# main.net
KiCad netlist of a schematic drawn in Altium Designer
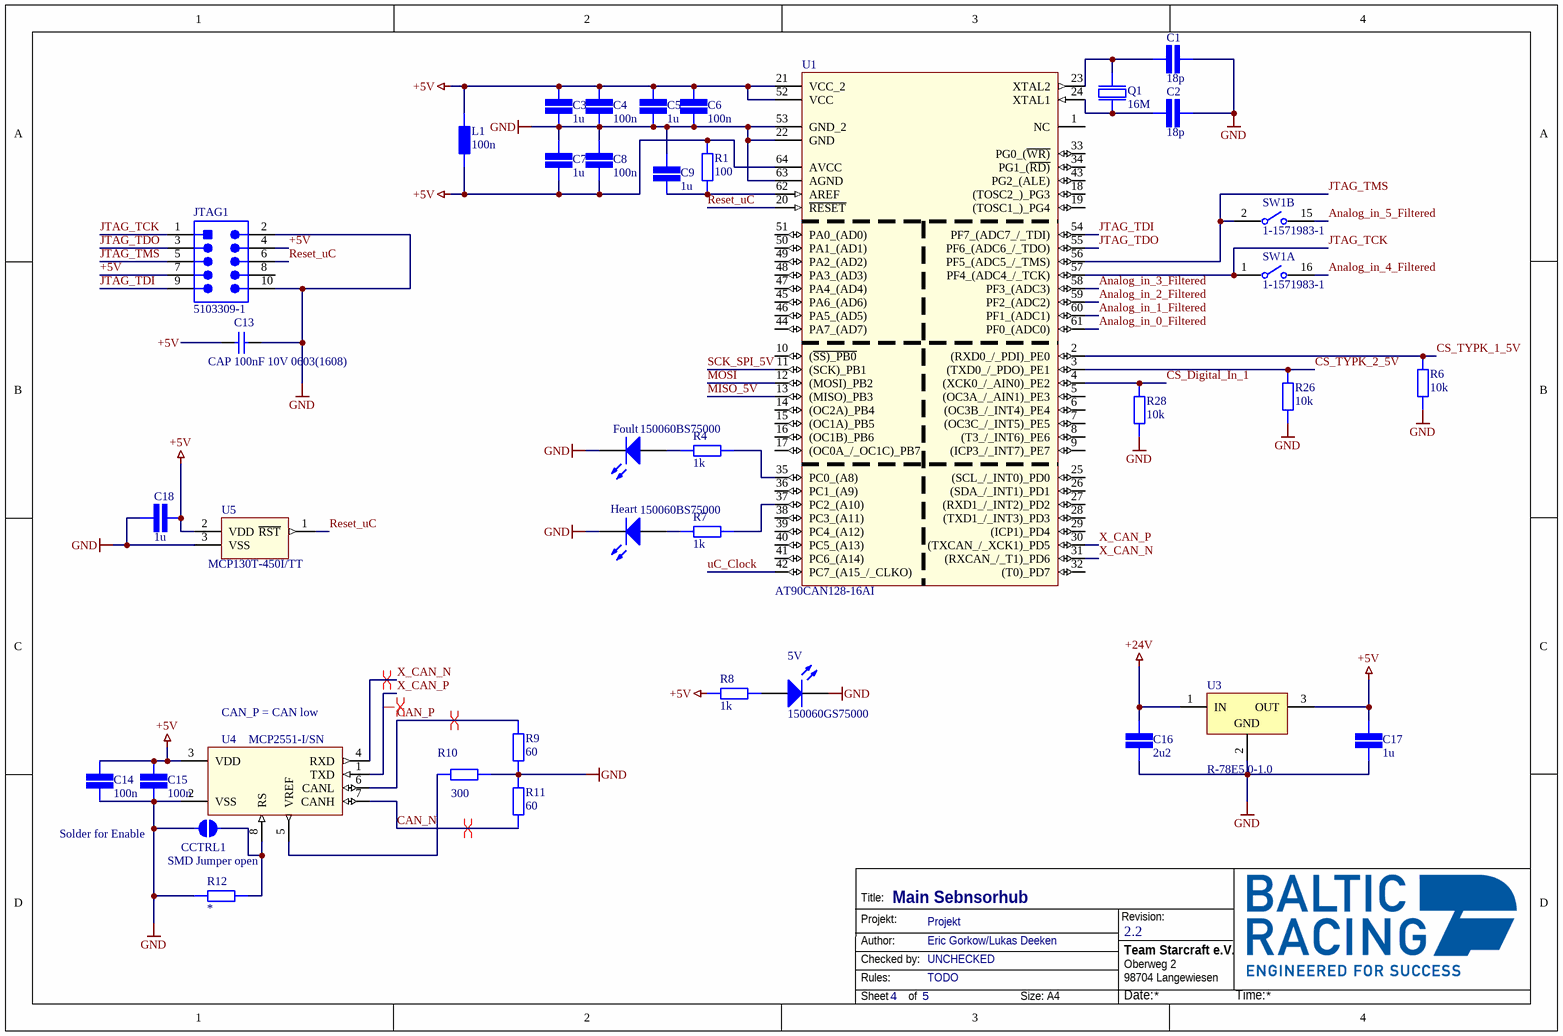
[diagram p0: main.SchDoc]

(export (version "E")
  (design (tool "Eeschema 10.0.6"))
  (components
    (comp (ref "5V")
      (value "150060GS75000")
      (footprint "0603_A")
      (description "SMD mono-color Chip LED, WL-SMCW, Green")
      (fields (field (name "MANUFACTURER") "Wuerth Elektronik"))
      (libsource (lib "Altium Content Vault") (part "WE-LED_K1A2-2"))
    )
    (comp (ref "C1")
      (value "18p")
      (footprint "CAP 0603/1608")
      (description "Capacitor with multiple Footprints")
      (fields (field (name "Comment") "SMD Capacitor"))
      (libsource (lib "") (part "SMD Capacitor_1"))
    )
    (comp (ref "C2")
      (value "18p")
      (footprint "CAP 0603/1608")
      (description "Capacitor with multiple Footprints")
      (fields (field (name "Comment") "SMD Capacitor"))
      (libsource (lib "") (part "SMD Capacitor_1"))
    )
    (comp (ref "C3")
      (value "1u")
      (footprint "CAP 0603/1608")
      (description "Capacitor with multiple Footprints")
      (fields (field (name "Comment") "SMD Capacitor"))
      (libsource (lib "Standardbauteile") (part "SMD Capacitor"))
    )
    (comp (ref "C4")
      (value "100n")
      (footprint "CAP 0603/1608")
      (description "Capacitor with multiple Footprints")
      (fields (field (name "Comment") "SMD Capacitor"))
      (libsource (lib "Standardbauteile") (part "SMD Capacitor"))
    )
    (comp (ref "C5")
      (value "1u")
      (footprint "CAP 0603/1608")
      (description "Capacitor with multiple Footprints")
      (fields (field (name "Comment") "SMD Capacitor"))
      (libsource (lib "Standardbauteile") (part "SMD Capacitor"))
    )
    (comp (ref "C6")
      (value "100n")
      (footprint "CAP 0603/1608")
      (description "Capacitor with multiple Footprints")
      (fields (field (name "Comment") "SMD Capacitor"))
      (libsource (lib "Standardbauteile") (part "SMD Capacitor"))
    )
    (comp (ref "C7")
      (value "1u")
      (footprint "CAP 0603/1608")
      (description "Capacitor with multiple Footprints")
      (fields (field (name "Comment") "SMD Capacitor"))
      (libsource (lib "Standardbauteile") (part "SMD Capacitor"))
    )
    (comp (ref "C8")
      (value "100n")
      (footprint "CAP 0603/1608")
      (description "Capacitor with multiple Footprints")
      (fields (field (name "Comment") "SMD Capacitor"))
      (libsource (lib "Standardbauteile") (part "SMD Capacitor"))
    )
    (comp (ref "C9")
      (value "1u")
      (footprint "CAP 0603/1608")
      (description "Capacitor with multiple Footprints")
      (fields (field (name "Comment") "SMD Capacitor"))
      (libsource (lib "Standardbauteile") (part "SMD Capacitor"))
    )
    (comp (ref "C13")
      (value "CAP 100nF 10V 0603(1608)")
      (footprint "CAPC0603(1608)100_L")
      (description "CAP 100nF 10V ±5% 0603 (1608 Metric) Thickness 1mm SMD")
      (fields (field (name "TOLERANCE") "Â±5%"))
      (libsource (lib "Altium Content Vault") (part "CAP"))
    )
    (comp (ref "C14")
      (value "100n")
      (footprint "CAP 0603/1608")
      (description "Capacitor with multiple Footprints")
      (fields (field (name "Comment") "SMD Capacitor"))
      (libsource (lib "Standardbauteile") (part "SMD Capacitor"))
    )
    (comp (ref "C15")
      (value "100n")
      (footprint "CAP 0603/1608")
      (description "Capacitor with multiple Footprints")
      (fields (field (name "Comment") "SMD Capacitor"))
      (libsource (lib "Standardbauteile") (part "SMD Capacitor"))
    )
    (comp (ref "C16")
      (value "2u2")
      (footprint "CAP 0603/1608")
      (description "Capacitor with multiple Footprints")
      (fields (field (name "Comment") "SMD Capacitor"))
      (libsource (lib "Standardbauteile") (part "SMD Capacitor"))
    )
    (comp (ref "C17")
      (value "1u")
      (footprint "CAP 0603/1608")
      (description "Capacitor with multiple Footprints")
      (fields (field (name "Comment") "SMD Capacitor"))
      (libsource (lib "Standardbauteile") (part "SMD Capacitor"))
    )
    (comp (ref "C18")
      (value "1u")
      (footprint "CAP 0603/1608")
      (description "Capacitor with multiple Footprints")
      (fields (field (name "Comment") "SMD Capacitor"))
      (libsource (lib "") (part "SMD Capacitor_1"))
    )
    (comp (ref "CCTRL1")
      (value "SMD Jumper open")
      (footprint "SMD-JUMPER-OPEN")
      (libsource (lib "Standardbauteile") (part "SMD Jumper open"))
    )
    (comp (ref "Foult")
      (value "150060BS75000")
      (footprint "0603_A")
      (description "SMD mono-color Chip LED, WL-SMCW, Blue")
      (fields (field (name "MANUFACTURER") "Wuerth Elektronik"))
      (libsource (lib "Altium Content Vault") (part "WE-LED_K1A2-2"))
    )
    (comp (ref "Heart")
      (value "150060BS75000")
      (footprint "0603_A")
      (description "SMD mono-color Chip LED, WL-SMCW, Blue")
      (fields (field (name "MANUFACTURER") "Wuerth Elektronik"))
      (libsource (lib "Altium Content Vault") (part "WE-LED_K1A2-2"))
    )
    (comp (ref "JTAG1")
      (value "5103309-1")
      (footprint "TECO-5103309-1_V")
      (fields (field (name "MANUFACTURER") "TE Connectivity"))
      (libsource (lib "Altium Content Vault") (part "CN-2P-M-R10"))
    )
    (comp (ref "L1")
      (value "100n")
      (footprint "STACKPOLE CSR0603")
      (fields (field (name "Comment") "SMD Inductor"))
      (libsource (lib "Standardbauteile") (part "SMD Inductor"))
    )
    (comp (ref "Q1")
      (value "16M")
      (footprint "NDK NX5032GA")
      (description "16 MHz Quartz")
      (libsource (lib "Standardbauteile") (part "16 MHz Quartz"))
    )
    (comp (ref "R1")
      (value "100")
      (footprint "STACKPOLE CSR0603")
      (description "Resistor with multiple footprints")
      (fields (field (name "Comment") "SMD Resistor"))
      (libsource (lib "Standardbauteile") (part "SMD Resistor"))
    )
    (comp (ref "R4")
      (value "1k")
      (footprint "STACKPOLE CSR0603")
      (description "Resistor with multiple footprints")
      (fields (field (name "Comment") "0603 220"))
      (libsource (lib "Standardbauteile") (part "SMD Resistor"))
    )
    (comp (ref "R6")
      (value "10k")
      (footprint "STACKPOLE CSR0603")
      (description "Resistor with multiple footprints")
      (fields (field (name "Comment") "SMD Resistor"))
      (libsource (lib "Standardbauteile") (part "SMD Resistor"))
    )
    (comp (ref "R7")
      (value "1k")
      (footprint "STACKPOLE CSR0603")
      (description "Resistor with multiple footprints")
      (fields (field (name "Comment") "0603 220"))
      (libsource (lib "Standardbauteile") (part "SMD Resistor"))
    )
    (comp (ref "R8")
      (value "1k")
      (footprint "STACKPOLE CSR0603")
      (description "Resistor with multiple footprints")
      (fields (field (name "Comment") "0603 220"))
      (libsource (lib "Standardbauteile") (part "SMD Resistor"))
    )
    (comp (ref "R9")
      (value "60")
      (footprint "STACKPOLE CSR0603")
      (description "Resistor with multiple footprints")
      (fields (field (name "Comment") "SMD Resistor"))
      (libsource (lib "Standardbauteile") (part "SMD Resistor"))
    )
    (comp (ref "R10")
      (value "300")
      (footprint "STACKPOLE CSR0603")
      (description "Resistor with multiple footprints")
      (fields (field (name "Comment") "SMD Resistor"))
      (libsource (lib "Standardbauteile") (part "SMD Resistor"))
    )
    (comp (ref "R11")
      (value "60")
      (footprint "STACKPOLE CSR0603")
      (description "Resistor with multiple footprints")
      (fields (field (name "Comment") "SMD Resistor"))
      (libsource (lib "Standardbauteile") (part "SMD Resistor"))
    )
    (comp (ref "R12")
      (value "SMD Resistor")
      (footprint "STACKPOLE CSR0603")
      (description "Resistor with multiple footprints")
      (fields (field (name "ALTIUM_VALUE") "*"))
      (libsource (lib "Standardbauteile") (part "SMD Resistor"))
    )
    (comp (ref "R26")
      (value "10k")
      (footprint "STACKPOLE CSR0603")
      (description "Resistor with multiple footprints")
      (fields (field (name "Comment") "SMD Resistor"))
      (libsource (lib "Standardbauteile") (part "SMD Resistor"))
    )
    (comp (ref "R28")
      (value "10k")
      (footprint "STACKPOLE CSR0603")
      (description "Resistor with multiple footprints")
      (fields (field (name "Comment") "SMD Resistor"))
      (libsource (lib "Standardbauteile") (part "SMD Resistor"))
    )
    (comp (ref "SW1")
      (value "1-1571983-1")
      (footprint "FP-1-1571983-1-MFG")
      (description "SWITCH SLIDE DIP SPST 25MA 24V")
      (fields
        (field (name "MANUFACTURER") "TE Connectivity")
        (field (name "OCTOPART") "https://octopart.com/1-1571983-1-te+connectivity-40115518")
      )
      (libsource (lib "Altium Content Vault") (part "970e54b12a704161c1b4a03f85903bf"))
    )
    (comp (ref "U1")
      (value "AT90CAN128-16AI")
      (footprint "*QFP80P1600X1600X120-64N")
      (description "Ic Mcu 8bit 128kb Flash 64tqfp")
      (fields (field (name "MF") "Microchip"))
      (libsource (lib "Eric") (part "AT90CAN128-16AI"))
    )
    (comp (ref "U3")
      (value "R-78E5.0-1.0")
      (footprint "SIP3_RECOM")
      (description "Nonisolated 5V Switchmode converter")
      (libsource (lib "Standardbauteile") (part "R-78E05-1.0"))
    )
    (comp (ref "U4")
      (value "MCP2551-I/SN")
      (footprint "*SOIC127P600X175-8N")
      (description "MCP2551 Series 5.5 V 1 Mb/s Surface Mount High-Speed CAN Transceiver - SOIC-8")
      (fields (field (name "MF") "Microchip"))
      (libsource (lib "Eric") (part "MCP2551-I/SN"))
    )
    (comp (ref "U5")
      (value "MCP130T-450I/TT")
      (footprint "*SOT95P237X112-3N")
      (description "System Supervisors - Power Supply Monitors with Reset Generators Open Drain Low")
      (fields (field (name "MF") "Microchip") (field (name "MP") "MCP120T-450I/TT"))
      (libsource (lib "Eric") (part "MCP130T-450I/TT"))
    )
  )
  (nets
    (net (code "1") (name "+5V") (class "Default")
      (node (ref "C13") (pin "1") (pinfunction "1_1") (pintype "passive"))
      (node (ref "C14") (pin "2") (pinfunction "2_2") (pintype "passive"))
      (node (ref "C15") (pin "2") (pinfunction "2_2") (pintype "passive"))
      (node (ref "C17") (pin "2") (pinfunction "2_2") (pintype "passive"))
      (node (ref "C18") (pin "1") (pinfunction "1_1") (pintype "passive"))
      (node (ref "C3") (pin "2") (pinfunction "2_2") (pintype "passive"))
      (node (ref "C4") (pin "2") (pinfunction "2_2") (pintype "passive"))
      (node (ref "C5") (pin "2") (pinfunction "2_2") (pintype "passive"))
      (node (ref "C6") (pin "2") (pinfunction "2_2") (pintype "passive"))
      (node (ref "C7") (pin "1") (pinfunction "1_1") (pintype "passive"))
      (node (ref "C8") (pin "1") (pinfunction "1_1") (pintype "passive"))
      (node (ref "JTAG1") (pin "4") (pinfunction "4_4") (pintype "passive"))
      (node (ref "JTAG1") (pin "7") (pinfunction "7_7") (pintype "passive"))
      (node (ref "L1") (pin "1") (pinfunction "1_1") (pintype "passive"))
      (node (ref "L1") (pin "2") (pinfunction "2_2") (pintype "passive"))
      (node (ref "R1") (pin "2") (pinfunction "2_2") (pintype "passive"))
      (node (ref "R8") (pin "1") (pinfunction "1_1") (pintype "passive"))
      (node (ref "U1") (pin "21") (pinfunction "VCC_2_21") (pintype "power_in"))
      (node (ref "U1") (pin "52") (pinfunction "VCC_52") (pintype "power_in"))
      (node (ref "U1") (pin "64") (pinfunction "AVCC_64") (pintype "power_in"))
      (node (ref "U3") (pin "3") (pinfunction "OUT_3") (pintype "power_in"))
      (node (ref "U4") (pin "3") (pinfunction "VDD_3") (pintype "power_in"))
      (node (ref "U5") (pin "2") (pinfunction "VDD_2") (pintype "power_in"))
    )
    (net (code "2") (name "+24V") (class "Default")
      (node (ref "C16") (pin "2") (pinfunction "2_2") (pintype "passive"))
      (node (ref "U3") (pin "1") (pinfunction "IN_1") (pintype "power_in"))
    )
    (net (code "3") (name "/Analog_in_0_Filtered") (class "Default")
      (node (ref "U1") (pin "61") (pinfunction "PF0_(ADC0)_61") (pintype "bidirectional"))
    )
    (net (code "4") (name "/Analog_in_1_Filtered") (class "Default")
      (node (ref "U1") (pin "60") (pinfunction "PF1_(ADC1)_60") (pintype "bidirectional"))
    )
    (net (code "5") (name "/Analog_in_2_Filtered") (class "Default")
      (node (ref "U1") (pin "59") (pinfunction "PF2_(ADC2)_59") (pintype "bidirectional"))
    )
    (net (code "6") (name "/Analog_in_3_Filtered") (class "Default")
      (node (ref "U1") (pin "58") (pinfunction "PF3_(ADC3)_58") (pintype "bidirectional"))
    )
    (net (code "7") (name "/Analog_in_4_Filtered") (class "Default")
      (node (ref "SW1") (pin "16") (pinfunction "16_16") (pintype "passive"))
    )
    (net (code "8") (name "/Analog_in_5_Filtered") (class "Default")
      (node (ref "SW1") (pin "15") (pinfunction "15_15") (pintype "passive"))
    )
    (net (code "9") (name "/CAN_N") (class "Default")
      (node (ref "R11") (pin "2") (pinfunction "2_2") (pintype "passive"))
      (node (ref "U4") (pin "7") (pinfunction "CANH_7") (pintype "bidirectional"))
    )
    (net (code "10") (name "/CAN_P") (class "Default")
      (node (ref "R9") (pin "1") (pinfunction "1_1") (pintype "passive"))
      (node (ref "U4") (pin "6") (pinfunction "CANL_6") (pintype "bidirectional"))
    )
    (net (code "11") (name "/CS_Digital_In_1") (class "Default")
      (node (ref "R28") (pin "2") (pinfunction "2_2") (pintype "passive"))
      (node (ref "U1") (pin "4") (pinfunction "(XCK0_/_AIN0)_PE2_4") (pintype "bidirectional"))
    )
    (net (code "12") (name "/CS_TYPK_1_5V") (class "Default")
      (node (ref "R6") (pin "2") (pinfunction "2_2") (pintype "passive"))
      (node (ref "U1") (pin "2") (pinfunction "(RXD0_/_PDI)_PE0_2") (pintype "bidirectional"))
    )
    (net (code "13") (name "/CS_TYPK_2_5V") (class "Default")
      (node (ref "R26") (pin "2") (pinfunction "2_2") (pintype "passive"))
      (node (ref "U1") (pin "3") (pinfunction "(TXD0_/_PDO)_PE1_3") (pintype "bidirectional"))
    )
    (net (code "14") (name "/JTAG_TCK") (class "Default")
      (node (ref "JTAG1") (pin "1") (pinfunction "1_1") (pintype "passive"))
      (node (ref "SW1") (pin "1") (pinfunction "1_1") (pintype "passive"))
      (node (ref "U1") (pin "57") (pinfunction "PF4_(ADC4_/_TCK)_57") (pintype "bidirectional"))
    )
    (net (code "15") (name "/JTAG_TDI") (class "Default")
      (node (ref "JTAG1") (pin "9") (pinfunction "9_9") (pintype "passive"))
      (node (ref "U1") (pin "54") (pinfunction "PF7_(ADC7_/_TDI)_54") (pintype "bidirectional"))
    )
    (net (code "16") (name "/JTAG_TDO") (class "Default")
      (node (ref "JTAG1") (pin "3") (pinfunction "3_3") (pintype "passive"))
      (node (ref "U1") (pin "55") (pinfunction "PF6_(ADC6_/_TDO)_55") (pintype "bidirectional"))
    )
    (net (code "17") (name "/JTAG_TMS") (class "Default")
      (node (ref "JTAG1") (pin "5") (pinfunction "5_5") (pintype "passive"))
      (node (ref "SW1") (pin "2") (pinfunction "2_2") (pintype "passive"))
      (node (ref "U1") (pin "56") (pinfunction "PF5_(ADC5_/_TMS)_56") (pintype "bidirectional"))
    )
    (net (code "18") (name "/MISO_5V") (class "Default")
      (node (ref "U1") (pin "13") (pinfunction "(MISO)_PB3_13") (pintype "bidirectional"))
    )
    (net (code "19") (name "/MOSI") (class "Default")
      (node (ref "U1") (pin "12") (pinfunction "(MOSI)_PB2_12") (pintype "bidirectional"))
    )
    (net (code "20") (name "/Reset_uC") (class "Default")
      (node (ref "JTAG1") (pin "6") (pinfunction "6_6") (pintype "passive"))
      (node (ref "U1") (pin "20") (pinfunction "~{RESET}_20") (pintype "input"))
      (node (ref "U5") (pin "1") (pinfunction "~{RST}_1") (pintype "output"))
    )
    (net (code "21") (name "/SCK_SPI_5V") (class "Default")
      (node (ref "U1") (pin "11") (pinfunction "(SCK)_PB1_11") (pintype "bidirectional"))
    )
    (net (code "22") (name "/X_CAN_N") (class "Default")
      (node (ref "U1") (pin "31") (pinfunction "(RXCAN_/_T1)_PD6_31") (pintype "bidirectional"))
      (node (ref "U4") (pin "4") (pinfunction "RXD_4") (pintype "output"))
    )
    (net (code "23") (name "/X_CAN_P") (class "Default")
      (node (ref "U1") (pin "30") (pinfunction "(TXCAN_/_XCK1)_PD5_30") (pintype "bidirectional"))
      (node (ref "U4") (pin "1") (pinfunction "TXD_1") (pintype "input"))
    )
    (net (code "24") (name "/uC_Clock") (class "Default")
      (node (ref "U1") (pin "42") (pinfunction "PC7_(A15_/_CLKO)_42") (pintype "bidirectional"))
    )
    (net (code "25") (name "GND") (class "Default")
      (node (ref "5V") (pin "1") (pinfunction "K_1") (pintype "passive"))
      (node (ref "C1") (pin "1") (pinfunction "1_1") (pintype "passive"))
      (node (ref "C13") (pin "2") (pinfunction "2_2") (pintype "passive"))
      (node (ref "C14") (pin "1") (pinfunction "1_1") (pintype "passive"))
      (node (ref "C15") (pin "1") (pinfunction "1_1") (pintype "passive"))
      (node (ref "C16") (pin "1") (pinfunction "1_1") (pintype "passive"))
      (node (ref "C17") (pin "1") (pinfunction "1_1") (pintype "passive"))
      (node (ref "C18") (pin "2") (pinfunction "2_2") (pintype "passive"))
      (node (ref "C2") (pin "1") (pinfunction "1_1") (pintype "passive"))
      (node (ref "C3") (pin "1") (pinfunction "1_1") (pintype "passive"))
      (node (ref "C4") (pin "1") (pinfunction "1_1") (pintype "passive"))
      (node (ref "C5") (pin "1") (pinfunction "1_1") (pintype "passive"))
      (node (ref "C6") (pin "1") (pinfunction "1_1") (pintype "passive"))
      (node (ref "C7") (pin "2") (pinfunction "2_2") (pintype "passive"))
      (node (ref "C8") (pin "2") (pinfunction "2_2") (pintype "passive"))
      (node (ref "C9") (pin "2") (pinfunction "2_2") (pintype "passive"))
      (node (ref "CCTRL1") (pin "1") (pinfunction "1_1") (pintype "passive"))
      (node (ref "Foult") (pin "1") (pinfunction "K_1") (pintype "passive"))
      (node (ref "Heart") (pin "1") (pinfunction "K_1") (pintype "passive"))
      (node (ref "JTAG1") (pin "10") (pinfunction "10_10") (pintype "passive"))
      (node (ref "JTAG1") (pin "2") (pinfunction "2_2") (pintype "passive"))
      (node (ref "R10") (pin "2") (pinfunction "2_2") (pintype "passive"))
      (node (ref "R11") (pin "1") (pinfunction "1_1") (pintype "passive"))
      (node (ref "R12") (pin "1") (pinfunction "1_1") (pintype "passive"))
      (node (ref "R26") (pin "1") (pinfunction "1_1") (pintype "passive"))
      (node (ref "R28") (pin "1") (pinfunction "1_1") (pintype "passive"))
      (node (ref "R6") (pin "1") (pinfunction "1_1") (pintype "passive"))
      (node (ref "R9") (pin "2") (pinfunction "2_2") (pintype "passive"))
      (node (ref "U1") (pin "22") (pinfunction "GND_22") (pintype "passive"))
      (node (ref "U1") (pin "53") (pinfunction "GND_2_53") (pintype "passive"))
      (node (ref "U1") (pin "63") (pinfunction "AGND_63") (pintype "passive"))
      (node (ref "U3") (pin "2") (pinfunction "GND_2") (pintype "power_in"))
      (node (ref "U4") (pin "2") (pinfunction "VSS_2") (pintype "passive"))
      (node (ref "U5") (pin "3") (pinfunction "VSS_3") (pintype "power_in"))
    )
    (net (code "26") (name "Net-(5V-A)") (class "Default")
      (node (ref "5V") (pin "2") (pinfunction "A_2") (pintype "passive"))
      (node (ref "R8") (pin "2") (pinfunction "2_2") (pintype "passive"))
    )
    (net (code "27") (name "Net-(Foult-A)") (class "Default")
      (node (ref "Foult") (pin "2") (pinfunction "A_2") (pintype "passive"))
      (node (ref "R4") (pin "1") (pinfunction "1_1") (pintype "passive"))
    )
    (net (code "28") (name "Net-(Heart-A)") (class "Default")
      (node (ref "Heart") (pin "2") (pinfunction "A_2") (pintype "passive"))
      (node (ref "R7") (pin "1") (pinfunction "1_1") (pintype "passive"))
    )
    (net (code "29") (name "Net-(U1-AREF)") (class "Default")
      (node (ref "C9") (pin "1") (pinfunction "1_1") (pintype "passive"))
      (node (ref "R1") (pin "1") (pinfunction "1_1") (pintype "passive"))
      (node (ref "U1") (pin "62") (pinfunction "AREF_62") (pintype "input"))
    )
    (net (code "30") (name "Net-(U1-PC0_(A8))") (class "Default")
      (node (ref "R4") (pin "2") (pinfunction "2_2") (pintype "passive"))
      (node (ref "U1") (pin "35") (pinfunction "PC0_(A8)_35") (pintype "bidirectional"))
    )
    (net (code "31") (name "Net-(U1-PC2_(A10))") (class "Default")
      (node (ref "R7") (pin "2") (pinfunction "2_2") (pintype "passive"))
      (node (ref "U1") (pin "37") (pinfunction "PC2_(A10)_37") (pintype "bidirectional"))
    )
    (net (code "32") (name "Net-(U1-XTAL1)") (class "Default")
      (node (ref "C2") (pin "2") (pinfunction "2_2") (pintype "passive"))
      (node (ref "Q1") (pin "1") (pinfunction "1_1") (pintype "passive"))
      (node (ref "U1") (pin "24") (pinfunction "XTAL1_24") (pintype "input"))
    )
    (net (code "33") (name "Net-(U1-XTAL2)") (class "Default")
      (node (ref "C1") (pin "2") (pinfunction "2_2") (pintype "passive"))
      (node (ref "Q1") (pin "2") (pinfunction "2_2") (pintype "passive"))
      (node (ref "U1") (pin "23") (pinfunction "XTAL2_23") (pintype "output"))
    )
    (net (code "34") (name "Net-(U4-RS)") (class "Default")
      (node (ref "CCTRL1") (pin "2") (pinfunction "2_2") (pintype "passive"))
      (node (ref "R12") (pin "2") (pinfunction "2_2") (pintype "passive"))
      (node (ref "U4") (pin "8") (pinfunction "RS_8") (pintype "input"))
    )
    (net (code "35") (name "Net-(U4-VREF)") (class "Default")
      (node (ref "R10") (pin "1") (pinfunction "1_1") (pintype "passive"))
      (node (ref "U4") (pin "5") (pinfunction "VREF_5") (pintype "output"))
    )
    (net (code "36") (name "unconnected-(JTAG1-Pad8)") (class "Default")
      (node (ref "JTAG1") (pin "8") (pinfunction "8_8") (pintype "passive"))
    )
    (net (code "37") (name "unconnected-(U1-(ICP1)_PD4-Pad29)") (class "Default")
      (node (ref "U1") (pin "29") (pinfunction "(ICP1)_PD4_29") (pintype "bidirectional"))
    )
    (net (code "38") (name "unconnected-(U1-(ICP3_{slash}_INT7)_PE7-Pad9)") (class "Default")
      (node (ref "U1") (pin "9") (pinfunction "(ICP3_/_INT7)_PE7_9") (pintype "bidirectional"))
    )
    (net (code "39") (name "unconnected-(U1-(OC0A_{slash}_OC1C)_PB7-Pad17)") (class "Default")
      (node (ref "U1") (pin "17") (pinfunction "(OC0A_/_OC1C)_PB7_17") (pintype "bidirectional"))
    )
    (net (code "40") (name "unconnected-(U1-(OC1A)_PB5-Pad15)") (class "Default")
      (node (ref "U1") (pin "15") (pinfunction "(OC1A)_PB5_15") (pintype "bidirectional"))
    )
    (net (code "41") (name "unconnected-(U1-(OC1B)_PB6-Pad16)") (class "Default")
      (node (ref "U1") (pin "16") (pinfunction "(OC1B)_PB6_16") (pintype "bidirectional"))
    )
    (net (code "42") (name "unconnected-(U1-(OC2A)_PB4-Pad14)") (class "Default")
      (node (ref "U1") (pin "14") (pinfunction "(OC2A)_PB4_14") (pintype "bidirectional"))
    )
    (net (code "43") (name "unconnected-(U1-(OC3A_{slash}_AIN1)_PE3-Pad5)") (class "Default")
      (node (ref "U1") (pin "5") (pinfunction "(OC3A_/_AIN1)_PE3_5") (pintype "bidirectional"))
    )
    (net (code "44") (name "unconnected-(U1-(OC3B_{slash}_INT4)_PE4-Pad6)") (class "Default")
      (node (ref "U1") (pin "6") (pinfunction "(OC3B_/_INT4)_PE4_6") (pintype "bidirectional"))
    )
    (net (code "45") (name "unconnected-(U1-(OC3C_{slash}_INT5)_PE5-Pad7)") (class "Default")
      (node (ref "U1") (pin "7") (pinfunction "(OC3C_/_INT5)_PE5_7") (pintype "bidirectional"))
    )
    (net (code "46") (name "unconnected-(U1-(RXD1_{slash}_INT2)_PD2-Pad27)") (class "Default")
      (node (ref "U1") (pin "27") (pinfunction "(RXD1_/_INT2)_PD2_27") (pintype "bidirectional"))
    )
    (net (code "47") (name "unconnected-(U1-(SCL_{slash}_INT0)_PD0-Pad25)") (class "Default")
      (node (ref "U1") (pin "25") (pinfunction "(SCL_/_INT0)_PD0_25") (pintype "bidirectional"))
    )
    (net (code "48") (name "unconnected-(U1-(SDA_{slash}_INT1)_PD1-Pad26)") (class "Default")
      (node (ref "U1") (pin "26") (pinfunction "(SDA_/_INT1)_PD1_26") (pintype "bidirectional"))
    )
    (net (code "49") (name "unconnected-(U1-(T0)_PD7-Pad32)") (class "Default")
      (node (ref "U1") (pin "32") (pinfunction "(T0)_PD7_32") (pintype "bidirectional"))
    )
    (net (code "50") (name "unconnected-(U1-(T3_{slash}_INT6)_PE6-Pad8)") (class "Default")
      (node (ref "U1") (pin "8") (pinfunction "(T3_/_INT6)_PE6_8") (pintype "bidirectional"))
    )
    (net (code "51") (name "unconnected-(U1-(TOSC1_)_PG4-Pad19)") (class "Default")
      (node (ref "U1") (pin "19") (pinfunction "(TOSC1_)_PG4_19") (pintype "bidirectional"))
    )
    (net (code "52") (name "unconnected-(U1-(TOSC2_)_PG3-Pad18)") (class "Default")
      (node (ref "U1") (pin "18") (pinfunction "(TOSC2_)_PG3_18") (pintype "bidirectional"))
    )
    (net (code "53") (name "unconnected-(U1-(TXD1_{slash}_INT3)_PD3-Pad28)") (class "Default")
      (node (ref "U1") (pin "28") (pinfunction "(TXD1_/_INT3)_PD3_28") (pintype "bidirectional"))
    )
    (net (code "54") (name "unconnected-(U1-(~{SS)_PB0}-Pad10)") (class "Default")
      (node (ref "U1") (pin "10") (pinfunction "(~{SS)_PB0}_10") (pintype "bidirectional"))
    )
    (net (code "55") (name "unconnected-(U1-NC-Pad1)") (class "Default")
      (node (ref "U1") (pin "1") (pinfunction "NC_1") (pintype "passive"))
    )
    (net (code "56") (name "unconnected-(U1-PA0_(AD0)-Pad51)") (class "Default")
      (node (ref "U1") (pin "51") (pinfunction "PA0_(AD0)_51") (pintype "bidirectional"))
    )
    (net (code "57") (name "unconnected-(U1-PA1_(AD1)-Pad50)") (class "Default")
      (node (ref "U1") (pin "50") (pinfunction "PA1_(AD1)_50") (pintype "bidirectional"))
    )
    (net (code "58") (name "unconnected-(U1-PA2_(AD2)-Pad49)") (class "Default")
      (node (ref "U1") (pin "49") (pinfunction "PA2_(AD2)_49") (pintype "bidirectional"))
    )
    (net (code "59") (name "unconnected-(U1-PA3_(AD3)-Pad48)") (class "Default")
      (node (ref "U1") (pin "48") (pinfunction "PA3_(AD3)_48") (pintype "bidirectional"))
    )
    (net (code "60") (name "unconnected-(U1-PA4_(AD4)-Pad47)") (class "Default")
      (node (ref "U1") (pin "47") (pinfunction "PA4_(AD4)_47") (pintype "bidirectional"))
    )
    (net (code "61") (name "unconnected-(U1-PA5_(AD5)-Pad46)") (class "Default")
      (node (ref "U1") (pin "46") (pinfunction "PA5_(AD5)_46") (pintype "bidirectional"))
    )
    (net (code "62") (name "unconnected-(U1-PA6_(AD6)-Pad45)") (class "Default")
      (node (ref "U1") (pin "45") (pinfunction "PA6_(AD6)_45") (pintype "bidirectional"))
    )
    (net (code "63") (name "unconnected-(U1-PA7_(AD7)-Pad44)") (class "Default")
      (node (ref "U1") (pin "44") (pinfunction "PA7_(AD7)_44") (pintype "bidirectional"))
    )
    (net (code "64") (name "unconnected-(U1-PC1_(A9)-Pad36)") (class "Default")
      (node (ref "U1") (pin "36") (pinfunction "PC1_(A9)_36") (pintype "bidirectional"))
    )
    (net (code "65") (name "unconnected-(U1-PC3_(A11)-Pad38)") (class "Default")
      (node (ref "U1") (pin "38") (pinfunction "PC3_(A11)_38") (pintype "bidirectional"))
    )
    (net (code "66") (name "unconnected-(U1-PC4_(A12)-Pad39)") (class "Default")
      (node (ref "U1") (pin "39") (pinfunction "PC4_(A12)_39") (pintype "bidirectional"))
    )
    (net (code "67") (name "unconnected-(U1-PC5_(A13)-Pad40)") (class "Default")
      (node (ref "U1") (pin "40") (pinfunction "PC5_(A13)_40") (pintype "bidirectional"))
    )
    (net (code "68") (name "unconnected-(U1-PC6_(A14)-Pad41)") (class "Default")
      (node (ref "U1") (pin "41") (pinfunction "PC6_(A14)_41") (pintype "bidirectional"))
    )
    (net (code "69") (name "unconnected-(U1-PG0_(~{WR)}-Pad33)") (class "Default")
      (node (ref "U1") (pin "33") (pinfunction "PG0_(~{WR)}_33") (pintype "bidirectional"))
    )
    (net (code "70") (name "unconnected-(U1-PG1_(~{RD)}-Pad34)") (class "Default")
      (node (ref "U1") (pin "34") (pinfunction "PG1_(~{RD)}_34") (pintype "bidirectional"))
    )
    (net (code "71") (name "unconnected-(U1-PG2_(ALE)-Pad43)") (class "Default")
      (node (ref "U1") (pin "43") (pinfunction "PG2_(ALE)_43") (pintype "bidirectional"))
    )
  )
)
